# Hybrid_control_v2.net
KiCad netlist of a schematic drawn in Altium Designer
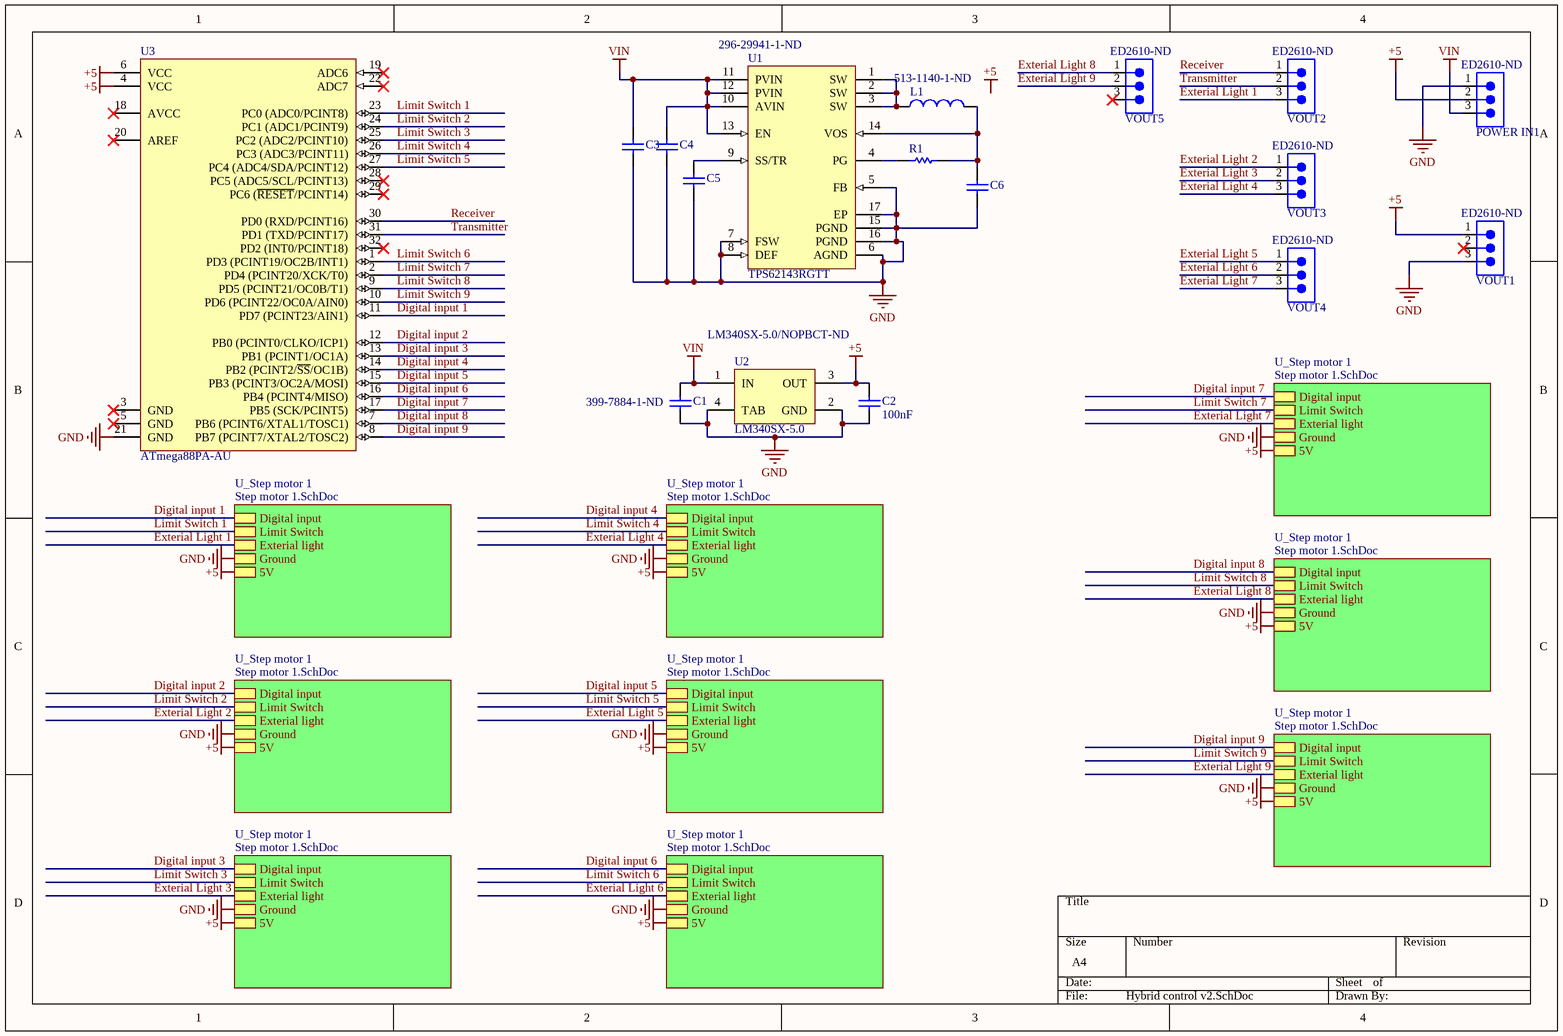
[diagram p0: Hybrid control v2.SchDoc]

(export (version "E")
  (design (tool "Eeschema 10.0.6"))
  (components
    (comp (ref "C1")
      (value "C0603C224K3RACTU")
      (footprint "CAPC1608X87X35ML15T15")
      (fields
        (field (name "MANUFACTURER") "Kemet")
        (field (name "SUPPLIER PART NUMBER 1") "399-7884-1-ND")
        (field (name "TOLERANCE") "10%")
        (field (name "VOLTAGE") "25V")
      )
      (libsource (lib "Altium Content Vault") (part "CAP"))
    )
    (comp (ref "C2")
      (value "C0402C104K8PAC7867")
      (footprint "CAPC1005X60X30ML05T10")
      (fields (field (name "MANUFACTURER") "Kemet") (field (name "C") "100nF"))
      (libsource (lib "Altium Content Vault") (part "CAP"))
    )
    (comp (ref "C3")
      (value "GRM21BR61E106KA73L")
      (footprint "CAPC2013X135X45ML10T25")
      (fields
        (field (name "MANUFACTURER") "Murata")
        (field (name "TOLERANCE") "10%")
        (field (name "VOLTAGE") "25V")
      )
      (libsource (lib "Altium Content Vault") (part "CAP"))
    )
    (comp (ref "C4")
      (value "GCM188L81H104KA57D")
      (footprint "CAPC1608X90X35NL10T15")
      (fields
        (field (name "MANUFACTURER") "Murata")
        (field (name "TOLERANCE") "10%")
        (field (name "VOLTAGE") "50V")
      )
      (libsource (lib "Altium Content Vault") (part "CAP"))
    )
    (comp (ref "C5")
      (value "CAP 3.3nF 50V 0603(1608)")
      (footprint "CAPC0603(1608)100_N")
      (description "CAP 3.3nF 50V ±10% 0603 (1608 Metric) Thickness 1mm SMD")
      (fields (field (name "TOLERANCE") "Â±10%") (field (name "VOLTAGE") "50V"))
      (libsource (lib "Altium Content Vault") (part "CAP"))
    )
    (comp (ref "C6")
      (value "GRM219R61A226MEA0D")
      (footprint "CAPC2013X95X45ML15T25")
      (fields
        (field (name "MANUFACTURER") "Murata")
        (field (name "TOLERANCE") "20%")
        (field (name "VOLTAGE") "10V")
      )
      (libsource (lib "Altium Content Vault") (part "CAP"))
    )
    (comp (ref "L1")
      (value "XFL4020-222MEC")
      (footprint "COIL-IND-2_V")
      (fields
        (field (name "MANUFACTURER") "Coilcraft")
        (field (name "TOLERANCE") "20%")
        (field (name "SUPPLIER PART NUMBER 2") "513-1140-1-ND")
      )
      (libsource (lib "Altium Content Vault") (part "IND-2"))
    )
    (comp (ref "POWER IN1")
      (value "1x3 header 90120-0123")
      (footprint "1x3 - OSTTC032162")
      (description "HDR 1x3, 2.54mm Pitch, Vert TH")
      (fields
        (field (name "MANUFACTURER PART #") "90120-0123")
        (field (name "MANUFACTURER") "Molex")
        (field (name "SUPPLIER PART NUMBER 2") "ED2610-ND")
      )
      (libsource (lib "Connectors") (part "1x3 header 90120-0123"))
    )
    (comp (ref "R1")
      (value "RC0603FR-07100KL")
      (footprint "RESC1608X55X25ML10T15")
      (description "Chip Resistor, 100 KOhm, +/- 1%, 0.1 W, -55 to 155 degC, 0603 (1608 Metric), RoHS, Tape and Reel")
      (fields (field (name "MANUFACTURER") "Yageo") (field (name "TOLERANCE") "1%"))
      (libsource (lib "Altium Content Vault") (part "RES-2"))
    )
    (comp (ref "U1")
      (value "TPS62143RGTT")
      (footprint "RGT0016C_V")
      (fields
        (field (name "MANUFACTURER") "Texas Instruments")
        (field (name "SUPPLIER PART NUMBER 1") "296-29941-1-ND")
      )
      (libsource (lib "Altium Content Vault") (part "TI-TPS62143RGT16-1700X1700TP"))
    )
    (comp (ref "U2")
      (value "LM340SX-5.0")
      (footprint "KTT0003B_M")
      (description "Series 3-Terminal Positive Regulators, 3-pin TO-263")
      (fields
        (field (name "MANUFACTURER") "Texas Instruments")
        (field (name "SUPPLIER PART NUMBER 1") "LM340SX-5.0/NOPBCT-ND")
      )
      (libsource (lib "Altium Content Vault") (part "PM-REG-LM2940-TO4"))
    )
    (comp (ref "U3")
      (value "ATmega88PA-AU")
      (footprint "32A_L")
      (libsource (lib "Altium Content Vault") (part "MC-8B-ATM48-SQ32"))
    )
    (comp (ref "VOUT1")
      (value "1x3 header 90120-0123")
      (footprint "1x3 - OSTTC032162")
      (description "HDR 1x3, 2.54mm Pitch, Vert TH")
      (fields
        (field (name "MANUFACTURER PART #") "90120-0123")
        (field (name "MANUFACTURER") "Molex")
        (field (name "SUPPLIER PART NUMBER 2") "ED2610-ND")
      )
      (libsource (lib "Connectors") (part "1x3 header 90120-0123"))
    )
    (comp (ref "VOUT2")
      (value "1x3 header 90120-0123")
      (footprint "1x3 - OSTTC032162")
      (description "HDR 1x3, 2.54mm Pitch, Vert TH")
      (fields
        (field (name "MANUFACTURER PART #") "90120-0123")
        (field (name "MANUFACTURER") "Molex")
        (field (name "SUPPLIER PART NUMBER 2") "ED2610-ND")
      )
      (libsource (lib "Connectors") (part "1x3 header 90120-0123"))
    )
    (comp (ref "VOUT3")
      (value "1x3 header 90120-0123")
      (footprint "1x3 - OSTTC032162")
      (description "HDR 1x3, 2.54mm Pitch, Vert TH")
      (fields
        (field (name "MANUFACTURER PART #") "90120-0123")
        (field (name "MANUFACTURER") "Molex")
        (field (name "SUPPLIER PART NUMBER 2") "ED2610-ND")
      )
      (libsource (lib "Connectors") (part "1x3 header 90120-0123"))
    )
    (comp (ref "VOUT4")
      (value "1x3 header 90120-0123")
      (footprint "1x3 - OSTTC032162")
      (description "HDR 1x3, 2.54mm Pitch, Vert TH")
      (fields
        (field (name "MANUFACTURER PART #") "90120-0123")
        (field (name "MANUFACTURER") "Molex")
        (field (name "SUPPLIER PART NUMBER 2") "ED2610-ND")
      )
      (libsource (lib "Connectors") (part "1x3 header 90120-0123"))
    )
    (comp (ref "VOUT5")
      (value "1x3 header 90120-0123")
      (footprint "1x3 - OSTTC032162")
      (description "HDR 1x3, 2.54mm Pitch, Vert TH")
      (fields
        (field (name "MANUFACTURER PART #") "90120-0123")
        (field (name "MANUFACTURER") "Molex")
        (field (name "SUPPLIER PART NUMBER 2") "ED2610-ND")
      )
      (libsource (lib "Connectors") (part "1x3 header 90120-0123"))
    )
  )
  (nets
    (net (code "1") (name "+5") (class "Default")
      (node (ref "C2") (pin "1") (pinfunction "1_1") (pintype "passive"))
      (node (ref "POWER IN1") (pin "2") (pinfunction "2_2") (pintype "passive"))
      (node (ref "U2") (pin "3") (pinfunction "OUT_3") (pintype "power_in"))
      (node (ref "U3") (pin "4") (pinfunction "VCC_4") (pintype "power_in"))
      (node (ref "U3") (pin "6") (pinfunction "VCC_6") (pintype "power_in"))
      (node (ref "VOUT1") (pin "1") (pinfunction "1_1") (pintype "passive"))
    )
    (net (code "2") (name "/Digital input 1") (class "Default")
      (node (ref "U3") (pin "11") (pinfunction "PD7_(PCINT23/AIN1)_11") (pintype "bidirectional"))
    )
    (net (code "3") (name "/Digital input 2") (class "Default")
      (node (ref "U3") (pin "12") (pinfunction "PB0_(PCINT0/CLKO/ICP1)_12") (pintype "bidirectional"))
    )
    (net (code "4") (name "/Digital input 3") (class "Default")
      (node (ref "U3") (pin "13") (pinfunction "PB1_(PCINT1/OC1A)_13") (pintype "bidirectional"))
    )
    (net (code "5") (name "/Digital input 4") (class "Default")
      (node (ref "U3") (pin "14") (pinfunction "PB2_(PCINT2/~{SS}/OC1B)_14") (pintype "bidirectional"))
    )
    (net (code "6") (name "/Digital input 5") (class "Default")
      (node (ref "U3") (pin "15") (pinfunction "PB3_(PCINT3/OC2A/MOSI)_15") (pintype "bidirectional"))
    )
    (net (code "7") (name "/Digital input 6") (class "Default")
      (node (ref "U3") (pin "16") (pinfunction "PB4_(PCINT4/MISO)_16") (pintype "bidirectional"))
    )
    (net (code "8") (name "/Digital input 7") (class "Default")
      (node (ref "U3") (pin "17") (pinfunction "PB5_(SCK/PCINT5)_17") (pintype "bidirectional"))
    )
    (net (code "9") (name "/Digital input 8") (class "Default")
      (node (ref "U3") (pin "7") (pinfunction "PB6_(PCINT6/XTAL1/TOSC1)_7") (pintype "bidirectional"))
    )
    (net (code "10") (name "/Digital input 9") (class "Default")
      (node (ref "U3") (pin "8") (pinfunction "PB7_(PCINT7/XTAL2/TOSC2)_8") (pintype "bidirectional"))
    )
    (net (code "11") (name "/Exterial Light 1") (class "Default")
      (node (ref "VOUT2") (pin "3") (pinfunction "3_3") (pintype "passive"))
    )
    (net (code "12") (name "/Exterial Light 2") (class "Default")
      (node (ref "VOUT3") (pin "1") (pinfunction "1_1") (pintype "passive"))
    )
    (net (code "13") (name "/Exterial Light 3") (class "Default")
      (node (ref "VOUT3") (pin "2") (pinfunction "2_2") (pintype "passive"))
    )
    (net (code "14") (name "/Exterial Light 4") (class "Default")
      (node (ref "VOUT3") (pin "3") (pinfunction "3_3") (pintype "passive"))
    )
    (net (code "15") (name "/Exterial Light 5") (class "Default")
      (node (ref "VOUT4") (pin "1") (pinfunction "1_1") (pintype "passive"))
    )
    (net (code "16") (name "/Exterial Light 6") (class "Default")
      (node (ref "VOUT4") (pin "2") (pinfunction "2_2") (pintype "passive"))
    )
    (net (code "17") (name "/Exterial Light 7") (class "Default")
      (node (ref "VOUT4") (pin "3") (pinfunction "3_3") (pintype "passive"))
    )
    (net (code "18") (name "/Exterial Light 8") (class "Default")
      (node (ref "VOUT5") (pin "1") (pinfunction "1_1") (pintype "passive"))
    )
    (net (code "19") (name "/Exterial Light 9") (class "Default")
      (node (ref "VOUT5") (pin "2") (pinfunction "2_2") (pintype "passive"))
    )
    (net (code "20") (name "/Limit Switch 1") (class "Default")
      (node (ref "U3") (pin "23") (pinfunction "PC0_(ADC0/PCINT8)_23") (pintype "bidirectional"))
    )
    (net (code "21") (name "/Limit Switch 2") (class "Default")
      (node (ref "U3") (pin "24") (pinfunction "PC1_(ADC1/PCINT9)_24") (pintype "bidirectional"))
    )
    (net (code "22") (name "/Limit Switch 3") (class "Default")
      (node (ref "U3") (pin "25") (pinfunction "PC2_(ADC2/PCINT10)_25") (pintype "bidirectional"))
    )
    (net (code "23") (name "/Limit Switch 4") (class "Default")
      (node (ref "U3") (pin "26") (pinfunction "PC3_(ADC3/PCINT11)_26") (pintype "bidirectional"))
    )
    (net (code "24") (name "/Limit Switch 5") (class "Default")
      (node (ref "U3") (pin "27") (pinfunction "PC4_(ADC4/SDA/PCINT12)_27") (pintype "bidirectional"))
    )
    (net (code "25") (name "/Limit Switch 6") (class "Default")
      (node (ref "U3") (pin "1") (pinfunction "PD3_(PCINT19/OC2B/INT1)_1") (pintype "bidirectional"))
    )
    (net (code "26") (name "/Limit Switch 7") (class "Default")
      (node (ref "U3") (pin "2") (pinfunction "PD4_(PCINT20/XCK/T0)_2") (pintype "bidirectional"))
    )
    (net (code "27") (name "/Limit Switch 8") (class "Default")
      (node (ref "U3") (pin "9") (pinfunction "PD5_(PCINT21/OC0B/T1)_9") (pintype "bidirectional"))
    )
    (net (code "28") (name "/Limit Switch 9") (class "Default")
      (node (ref "U3") (pin "10") (pinfunction "PD6_(PCINT22/OC0A/AIN0)_10") (pintype "bidirectional"))
    )
    (net (code "29") (name "/Receiver") (class "Default")
      (node (ref "U3") (pin "30") (pinfunction "PD0_(RXD/PCINT16)_30") (pintype "bidirectional"))
      (node (ref "VOUT2") (pin "1") (pinfunction "1_1") (pintype "passive"))
    )
    (net (code "30") (name "/Transmitter") (class "Default")
      (node (ref "U3") (pin "31") (pinfunction "PD1_(TXD/PCINT17)_31") (pintype "bidirectional"))
      (node (ref "VOUT2") (pin "2") (pinfunction "2_2") (pintype "passive"))
    )
    (net (code "31") (name "GND") (class "Default")
      (node (ref "C1") (pin "1") (pinfunction "1_1") (pintype "passive"))
      (node (ref "C2") (pin "2") (pinfunction "2_2") (pintype "passive"))
      (node (ref "C3") (pin "1") (pinfunction "1_1") (pintype "passive"))
      (node (ref "C4") (pin "1") (pinfunction "1_1") (pintype "passive"))
      (node (ref "C5") (pin "1") (pinfunction "1_1") (pintype "passive"))
      (node (ref "C6") (pin "1") (pinfunction "1_1") (pintype "passive"))
      (node (ref "POWER IN1") (pin "1") (pinfunction "1_1") (pintype "passive"))
      (node (ref "U1") (pin "15") (pinfunction "PGND_15") (pintype "power_in"))
      (node (ref "U1") (pin "16") (pinfunction "PGND_16") (pintype "power_in"))
      (node (ref "U1") (pin "17") (pinfunction "EP_17") (pintype "power_in"))
      (node (ref "U1") (pin "5") (pinfunction "FB_5") (pintype "input"))
      (node (ref "U1") (pin "6") (pinfunction "AGND_6") (pintype "power_in"))
      (node (ref "U1") (pin "7") (pinfunction "FSW_7") (pintype "input"))
      (node (ref "U1") (pin "8") (pinfunction "DEF_8") (pintype "input"))
      (node (ref "U2") (pin "2") (pinfunction "GND_2") (pintype "power_in"))
      (node (ref "U2") (pin "4") (pinfunction "TAB_4") (pintype "power_in"))
      (node (ref "U3") (pin "21") (pinfunction "GND_21") (pintype "power_in"))
      (node (ref "VOUT1") (pin "3") (pinfunction "3_3") (pintype "passive"))
    )
    (net (code "32") (name "Net-(L1-Pad1)") (class "Default")
      (node (ref "L1") (pin "1") (pinfunction "1_1") (pintype "passive"))
      (node (ref "U1") (pin "1") (pinfunction "SW_1") (pintype "power_in"))
      (node (ref "U1") (pin "2") (pinfunction "SW_2") (pintype "power_in"))
      (node (ref "U1") (pin "3") (pinfunction "SW_3") (pintype "power_in"))
    )
    (net (code "33") (name "Net-(U1-PG)") (class "Default")
      (node (ref "R1") (pin "1") (pinfunction "1_1") (pintype "passive"))
      (node (ref "U1") (pin "4") (pinfunction "PG_4") (pintype "tri_state"))
    )
    (net (code "34") (name "Net-(U1-SS{slash}TR)") (class "Default")
      (node (ref "C5") (pin "2") (pinfunction "2_2") (pintype "passive"))
      (node (ref "U1") (pin "9") (pinfunction "SS/TR_9") (pintype "input"))
    )
    (net (code "35") (name "Net-(U1-VOS)") (class "Default")
      (node (ref "C6") (pin "2") (pinfunction "2_2") (pintype "passive"))
      (node (ref "L1") (pin "2") (pinfunction "2_2") (pintype "passive"))
      (node (ref "R1") (pin "2") (pinfunction "2_2") (pintype "passive"))
      (node (ref "U1") (pin "14") (pinfunction "VOS_14") (pintype "input"))
    )
    (net (code "36") (name "VIN") (class "Default")
      (node (ref "C1") (pin "2") (pinfunction "2_2") (pintype "passive"))
      (node (ref "C3") (pin "2") (pinfunction "2_2") (pintype "passive"))
      (node (ref "C4") (pin "2") (pinfunction "2_2") (pintype "passive"))
      (node (ref "POWER IN1") (pin "3") (pinfunction "3_3") (pintype "passive"))
      (node (ref "U1") (pin "10") (pinfunction "AVIN_10") (pintype "power_in"))
      (node (ref "U1") (pin "11") (pinfunction "PVIN_11") (pintype "power_in"))
      (node (ref "U1") (pin "12") (pinfunction "PVIN_12") (pintype "power_in"))
      (node (ref "U1") (pin "13") (pinfunction "EN_13") (pintype "input"))
      (node (ref "U2") (pin "1") (pinfunction "IN_1") (pintype "power_in"))
    )
    (net (code "37") (name "unconnected-(U3-ADC6-Pad19)") (class "Default")
      (node (ref "U3") (pin "19") (pinfunction "ADC6_19") (pintype "input+no_connect"))
    )
    (net (code "38") (name "unconnected-(U3-ADC7-Pad22)") (class "Default")
      (node (ref "U3") (pin "22") (pinfunction "ADC7_22") (pintype "input+no_connect"))
    )
    (net (code "39") (name "unconnected-(U3-AREF-Pad20)") (class "Default")
      (node (ref "U3") (pin "20") (pinfunction "AREF_20") (pintype "passive+no_connect"))
    )
    (net (code "40") (name "unconnected-(U3-AVCC-Pad18)") (class "Default")
      (node (ref "U3") (pin "18") (pinfunction "AVCC_18") (pintype "power_in+no_connect"))
    )
    (net (code "41") (name "unconnected-(U3-GND-Pad3)") (class "Default")
      (node (ref "U3") (pin "3") (pinfunction "GND_3") (pintype "power_in+no_connect"))
    )
    (net (code "42") (name "unconnected-(U3-GND-Pad5)") (class "Default")
      (node (ref "U3") (pin "5") (pinfunction "GND_5") (pintype "power_in+no_connect"))
    )
    (net (code "43") (name "unconnected-(U3-PC5_(ADC5{slash}SCL{slash}PCINT13)-Pad28)") (class "Default")
      (node (ref "U3") (pin "28") (pinfunction "PC5_(ADC5/SCL/PCINT13)_28") (pintype "bidirectional+no_connect"))
    )
    (net (code "44") (name "unconnected-(U3-PC6_(~{RESET}{slash}PCINT14)-Pad29)") (class "Default")
      (node (ref "U3") (pin "29") (pinfunction "PC6_(~{RESET}/PCINT14)_29") (pintype "bidirectional+no_connect"))
    )
    (net (code "45") (name "unconnected-(U3-PD2_(INT0{slash}PCINT18)-Pad32)") (class "Default")
      (node (ref "U3") (pin "32") (pinfunction "PD2_(INT0/PCINT18)_32") (pintype "bidirectional+no_connect"))
    )
    (net (code "46") (name "unconnected-(VOUT1-Pad2)") (class "Default")
      (node (ref "VOUT1") (pin "2") (pinfunction "2_2") (pintype "passive+no_connect"))
    )
    (net (code "47") (name "unconnected-(VOUT5-Pad3)") (class "Default")
      (node (ref "VOUT5") (pin "3") (pinfunction "3_3") (pintype "passive+no_connect"))
    )
  )
)
